# Ornament.net
KiCad netlist of a schematic drawn in EAGLE
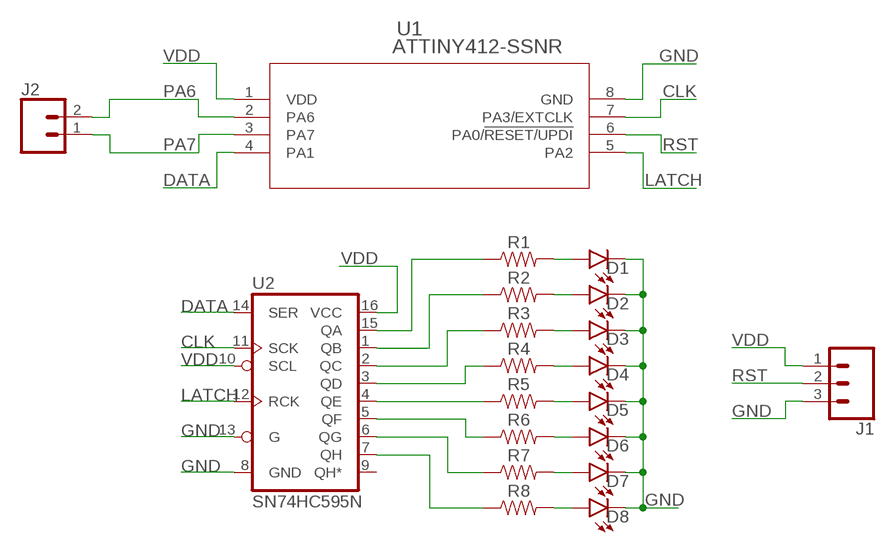
[diagram p0: schematic, sheet 1]

(export (version "E")
  (design (tool "Eeschema 10.0.6"))
  (components
    (comp (ref "D1")
      (value "LED5MM")
      (footprint "eagle-import:LED_5MM")
      (libsource (lib "eagle-import") (part "LED5MM"))
    )
    (comp (ref "D2")
      (value "LED5MM")
      (footprint "eagle-import:LED_5MM")
      (libsource (lib "eagle-import") (part "LED5MM"))
    )
    (comp (ref "D3")
      (value "LED5MM")
      (footprint "eagle-import:LED_5MM")
      (libsource (lib "eagle-import") (part "LED5MM"))
    )
    (comp (ref "D4")
      (value "LED5MM")
      (footprint "eagle-import:LED_5MM")
      (libsource (lib "eagle-import") (part "LED5MM"))
    )
    (comp (ref "D5")
      (value "LED5MM")
      (footprint "eagle-import:LED_5MM")
      (libsource (lib "eagle-import") (part "LED5MM"))
    )
    (comp (ref "D6")
      (value "LED5MM")
      (footprint "eagle-import:LED_5MM")
      (libsource (lib "eagle-import") (part "LED5MM"))
    )
    (comp (ref "D7")
      (value "LED5MM")
      (footprint "eagle-import:LED_5MM")
      (libsource (lib "eagle-import") (part "LED5MM"))
    )
    (comp (ref "D8")
      (value "LED5MM")
      (footprint "eagle-import:LED_5MM")
      (libsource (lib "eagle-import") (part "LED5MM"))
    )
    (comp (ref "J1")
      (value "CONN_03")
      (footprint "eagle-import:1X03")
      (libsource (lib "eagle-import") (part "CONN_03"))
    )
    (comp (ref "J2")
      (value "CONN_02")
      (footprint "eagle-import:1X02")
      (libsource (lib "eagle-import") (part "CONN_02"))
    )
    (comp (ref "R1")
      (value "RESISTOR1206")
      (footprint "eagle-import:1206")
      (libsource (lib "eagle-import") (part "RESISTOR1206"))
    )
    (comp (ref "R2")
      (value "RESISTOR1206")
      (footprint "eagle-import:1206")
      (libsource (lib "eagle-import") (part "RESISTOR1206"))
    )
    (comp (ref "R3")
      (value "RESISTOR1206")
      (footprint "eagle-import:1206")
      (libsource (lib "eagle-import") (part "RESISTOR1206"))
    )
    (comp (ref "R4")
      (value "RESISTOR1206")
      (footprint "eagle-import:1206")
      (libsource (lib "eagle-import") (part "RESISTOR1206"))
    )
    (comp (ref "R5")
      (value "RESISTOR1206")
      (footprint "eagle-import:1206")
      (libsource (lib "eagle-import") (part "RESISTOR1206"))
    )
    (comp (ref "R6")
      (value "RESISTOR1206")
      (footprint "eagle-import:1206")
      (libsource (lib "eagle-import") (part "RESISTOR1206"))
    )
    (comp (ref "R7")
      (value "RESISTOR1206")
      (footprint "eagle-import:1206")
      (libsource (lib "eagle-import") (part "RESISTOR1206"))
    )
    (comp (ref "R8")
      (value "RESISTOR1206")
      (footprint "eagle-import:1206")
      (libsource (lib "eagle-import") (part "RESISTOR1206"))
    )
    (comp (ref "U1")
      (value "ATTINY412-SSNR")
      (footprint "eagle-import:SOIC8_SA_SST_MCH")
      (fields
        (field (name "MANUFACTURER_PART_NUMBER") "ATTINY412")
        (field (name "COPYRIGHT") "Copyright (C) 2018 Accelerated Designs. All rights reserved")
      )
      (libsource (lib "eagle-import") (part "ATTINY412-SSNR"))
    )
    (comp (ref "U2")
      (value "SN74HC595N")
      (footprint "eagle-import:DIP16")
      (libsource (lib "eagle-import") (part "74595NHC"))
    )
  )
  (nets
    (net (code "1") (name "/CLK") (class "Default")
      (node (ref "U1") (pin "7") (pinfunction "PA3/EXTCLK_7") (pintype "bidirectional"))
      (node (ref "U2") (pin "11") (pinfunction "SCK_11") (pintype "input"))
    )
    (net (code "2") (name "/DATA") (class "Default")
      (node (ref "U1") (pin "4") (pinfunction "PA1_4") (pintype "bidirectional"))
      (node (ref "U2") (pin "14") (pinfunction "SER_14") (pintype "input"))
    )
    (net (code "3") (name "/GND") (class "Default")
      (node (ref "D1") (pin "K") (pinfunction "C_K") (pintype "passive"))
      (node (ref "D2") (pin "K") (pinfunction "C_K") (pintype "passive"))
      (node (ref "D3") (pin "K") (pinfunction "C_K") (pintype "passive"))
      (node (ref "D4") (pin "K") (pinfunction "C_K") (pintype "passive"))
      (node (ref "D5") (pin "K") (pinfunction "C_K") (pintype "passive"))
      (node (ref "D6") (pin "K") (pinfunction "C_K") (pintype "passive"))
      (node (ref "D7") (pin "K") (pinfunction "C_K") (pintype "passive"))
      (node (ref "D8") (pin "K") (pinfunction "C_K") (pintype "passive"))
      (node (ref "J1") (pin "3") (pinfunction "3_3") (pintype "passive"))
      (node (ref "U1") (pin "8") (pinfunction "GND_8") (pintype "passive"))
      (node (ref "U2") (pin "13") (pinfunction "G_13") (pintype "input"))
      (node (ref "U2") (pin "8") (pinfunction "GND_8") (pintype "power_in"))
    )
    (net (code "4") (name "/LATCH") (class "Default")
      (node (ref "U1") (pin "5") (pinfunction "PA2_5") (pintype "bidirectional"))
      (node (ref "U2") (pin "12") (pinfunction "RCK_12") (pintype "input"))
    )
    (net (code "5") (name "/PA6") (class "Default")
      (node (ref "J2") (pin "2") (pinfunction "2_2") (pintype "passive"))
      (node (ref "U1") (pin "2") (pinfunction "PA6_2") (pintype "bidirectional"))
    )
    (net (code "6") (name "/PA7") (class "Default")
      (node (ref "J2") (pin "1") (pinfunction "1_1") (pintype "passive"))
      (node (ref "U1") (pin "3") (pinfunction "PA7_3") (pintype "bidirectional"))
    )
    (net (code "7") (name "/RST") (class "Default")
      (node (ref "J1") (pin "2") (pinfunction "2_2") (pintype "passive"))
      (node (ref "U1") (pin "6") (pinfunction "PA0/~{RESET/UPDI}_6") (pintype "bidirectional"))
    )
    (net (code "8") (name "/VDD") (class "Default")
      (node (ref "J1") (pin "1") (pinfunction "1_1") (pintype "passive"))
      (node (ref "U1") (pin "1") (pinfunction "VDD_1") (pintype "power_in"))
      (node (ref "U2") (pin "10") (pinfunction "SCL_10") (pintype "input"))
      (node (ref "U2") (pin "16") (pinfunction "VCC_16") (pintype "power_in"))
    )
    (net (code "9") (name "Net-(D1-PadA)") (class "Default")
      (node (ref "D1") (pin "A") (pinfunction "A_A") (pintype "passive"))
      (node (ref "R1") (pin "2") (pinfunction "2_2") (pintype "passive"))
    )
    (net (code "10") (name "Net-(D2-PadA)") (class "Default")
      (node (ref "D2") (pin "A") (pinfunction "A_A") (pintype "passive"))
      (node (ref "R2") (pin "2") (pinfunction "2_2") (pintype "passive"))
    )
    (net (code "11") (name "Net-(D3-PadA)") (class "Default")
      (node (ref "D3") (pin "A") (pinfunction "A_A") (pintype "passive"))
      (node (ref "R3") (pin "2") (pinfunction "2_2") (pintype "passive"))
    )
    (net (code "12") (name "Net-(D4-PadA)") (class "Default")
      (node (ref "D4") (pin "A") (pinfunction "A_A") (pintype "passive"))
      (node (ref "R4") (pin "2") (pinfunction "2_2") (pintype "passive"))
    )
    (net (code "13") (name "Net-(D5-PadA)") (class "Default")
      (node (ref "D5") (pin "A") (pinfunction "A_A") (pintype "passive"))
      (node (ref "R5") (pin "2") (pinfunction "2_2") (pintype "passive"))
    )
    (net (code "14") (name "Net-(D6-PadA)") (class "Default")
      (node (ref "D6") (pin "A") (pinfunction "A_A") (pintype "passive"))
      (node (ref "R6") (pin "2") (pinfunction "2_2") (pintype "passive"))
    )
    (net (code "15") (name "Net-(D7-PadA)") (class "Default")
      (node (ref "D7") (pin "A") (pinfunction "A_A") (pintype "passive"))
      (node (ref "R7") (pin "2") (pinfunction "2_2") (pintype "passive"))
    )
    (net (code "16") (name "Net-(D8-PadA)") (class "Default")
      (node (ref "D8") (pin "A") (pinfunction "A_A") (pintype "passive"))
      (node (ref "R8") (pin "2") (pinfunction "2_2") (pintype "passive"))
    )
    (net (code "17") (name "Net-(U2-QA)") (class "Default")
      (node (ref "R1") (pin "1") (pinfunction "1_1") (pintype "passive"))
      (node (ref "U2") (pin "15") (pinfunction "QA_15") (pintype "tri_state"))
    )
    (net (code "18") (name "Net-(U2-QB)") (class "Default")
      (node (ref "R2") (pin "1") (pinfunction "1_1") (pintype "passive"))
      (node (ref "U2") (pin "1") (pinfunction "QB_1") (pintype "tri_state"))
    )
    (net (code "19") (name "Net-(U2-QC)") (class "Default")
      (node (ref "R3") (pin "1") (pinfunction "1_1") (pintype "passive"))
      (node (ref "U2") (pin "2") (pinfunction "QC_2") (pintype "tri_state"))
    )
    (net (code "20") (name "Net-(U2-QD)") (class "Default")
      (node (ref "R4") (pin "1") (pinfunction "1_1") (pintype "passive"))
      (node (ref "U2") (pin "3") (pinfunction "QD_3") (pintype "tri_state"))
    )
    (net (code "21") (name "Net-(U2-QE)") (class "Default")
      (node (ref "R5") (pin "1") (pinfunction "1_1") (pintype "passive"))
      (node (ref "U2") (pin "4") (pinfunction "QE_4") (pintype "tri_state"))
    )
    (net (code "22") (name "Net-(U2-QF)") (class "Default")
      (node (ref "R6") (pin "1") (pinfunction "1_1") (pintype "passive"))
      (node (ref "U2") (pin "5") (pinfunction "QF_5") (pintype "tri_state"))
    )
    (net (code "23") (name "Net-(U2-QG)") (class "Default")
      (node (ref "R7") (pin "1") (pinfunction "1_1") (pintype "passive"))
      (node (ref "U2") (pin "6") (pinfunction "QG_6") (pintype "tri_state"))
    )
    (net (code "24") (name "Net-(U2-QH)") (class "Default")
      (node (ref "R8") (pin "1") (pinfunction "1_1") (pintype "passive"))
      (node (ref "U2") (pin "7") (pinfunction "QH_7") (pintype "tri_state"))
    )
    (net (code "25") (name "unconnected-(U2-QH*-Pad9)") (class "Default")
      (node (ref "U2") (pin "9") (pinfunction "QH*_9") (pintype "tri_state"))
    )
  )
)
